# Branch_Left.net
KiCad netlist of a schematic drawn in EAGLE
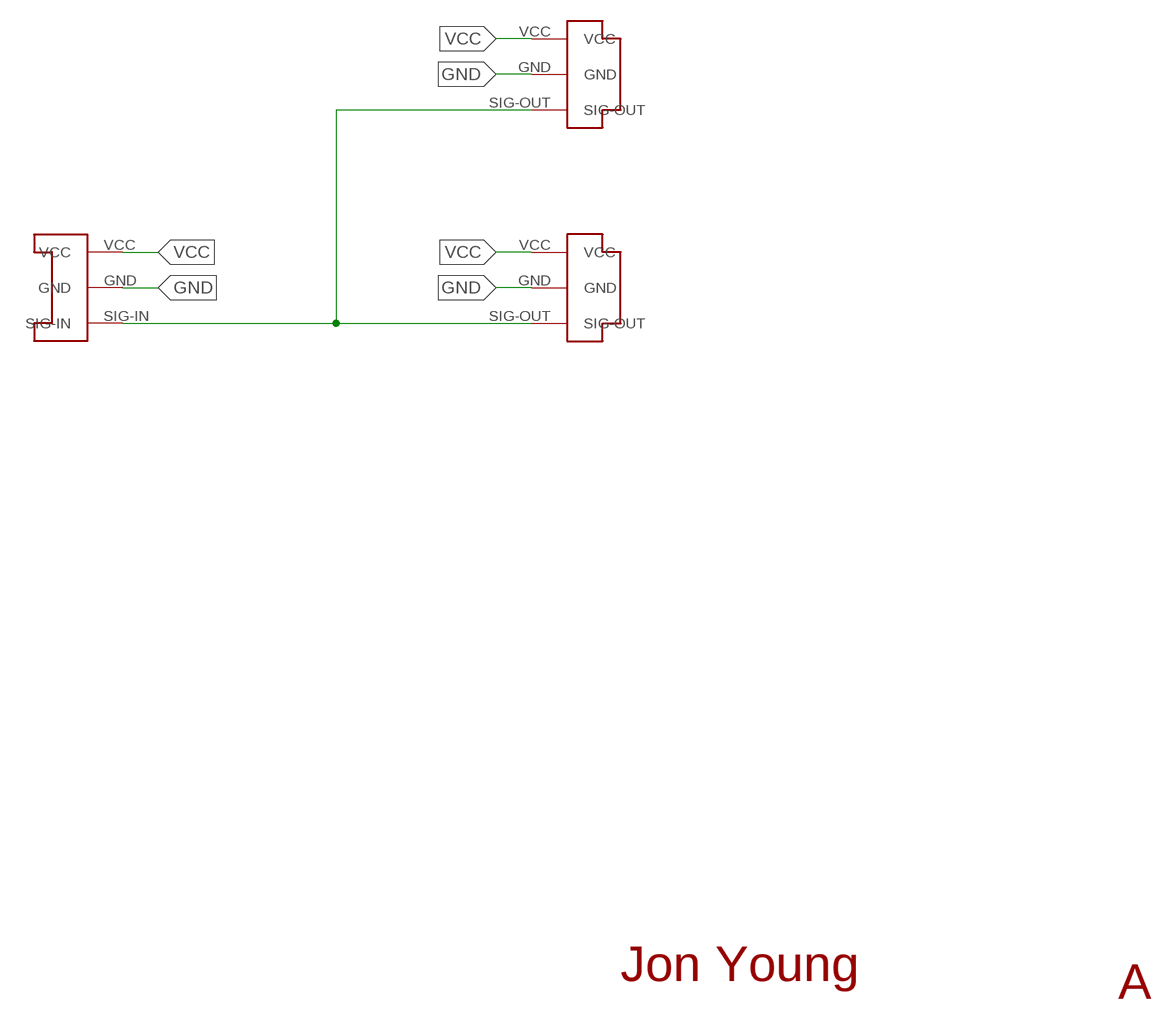
[diagram p0: schematic, sheet 1]

(export (version "E")
  (design (tool "Eeschema 10.0.6"))
  (components
    (comp (ref "U$1")
      (value "CONN-PLUG-3POS-3MM")
      (footprint "eagle-import:PLUG-3POS-3MM-SMD")
      (libsource (lib "eagle-import") (part "CONN-PLUG-3POS-3MM"))
    )
    (comp (ref "U$2")
      (value "CONN-SOCKET-3POS-3MM")
      (footprint "eagle-import:SOCKET-3POS-3MM-SMD")
      (libsource (lib "eagle-import") (part "CONN-SOCKET-3POS-3MM"))
    )
    (comp (ref "U$4")
      (value "CONN-PLUG-3POS-3MM")
      (footprint "eagle-import:PLUG-3POS-3MM-SMD")
      (libsource (lib "eagle-import") (part "CONN-PLUG-3POS-3MM"))
    )
  )
  (nets
    (net (code "1") (name "GND") (class "Default")
      (node (ref "U$1") (pin "GND") (pinfunction "GND_GND") (pintype "power_in"))
      (node (ref "U$2") (pin "GND") (pinfunction "GND_GND") (pintype "power_in"))
      (node (ref "U$4") (pin "GND") (pinfunction "GND_GND") (pintype "power_in"))
    )
    (net (code "2") (name "Net-(U$1-PadSIG-OUT)") (class "Default")
      (node (ref "U$1") (pin "SIG-OUT") (pinfunction "SIG-OUT_SIG-OUT") (pintype "bidirectional"))
      (node (ref "U$2") (pin "SIG-IN") (pinfunction "SIG-IN_SIG-IN") (pintype "bidirectional"))
      (node (ref "U$4") (pin "SIG-OUT") (pinfunction "SIG-OUT_SIG-OUT") (pintype "bidirectional"))
    )
    (net (code "3") (name "VCC") (class "Default")
      (node (ref "U$1") (pin "VCC") (pinfunction "VCC_VCC") (pintype "power_in"))
      (node (ref "U$2") (pin "VCC") (pinfunction "VCC_VCC") (pintype "power_in"))
      (node (ref "U$4") (pin "VCC") (pinfunction "VCC_VCC") (pintype "power_in"))
    )
  )
)
